# easy_eda_project.net
KiCad netlist of a schematic drawn in EasyEDA Pro
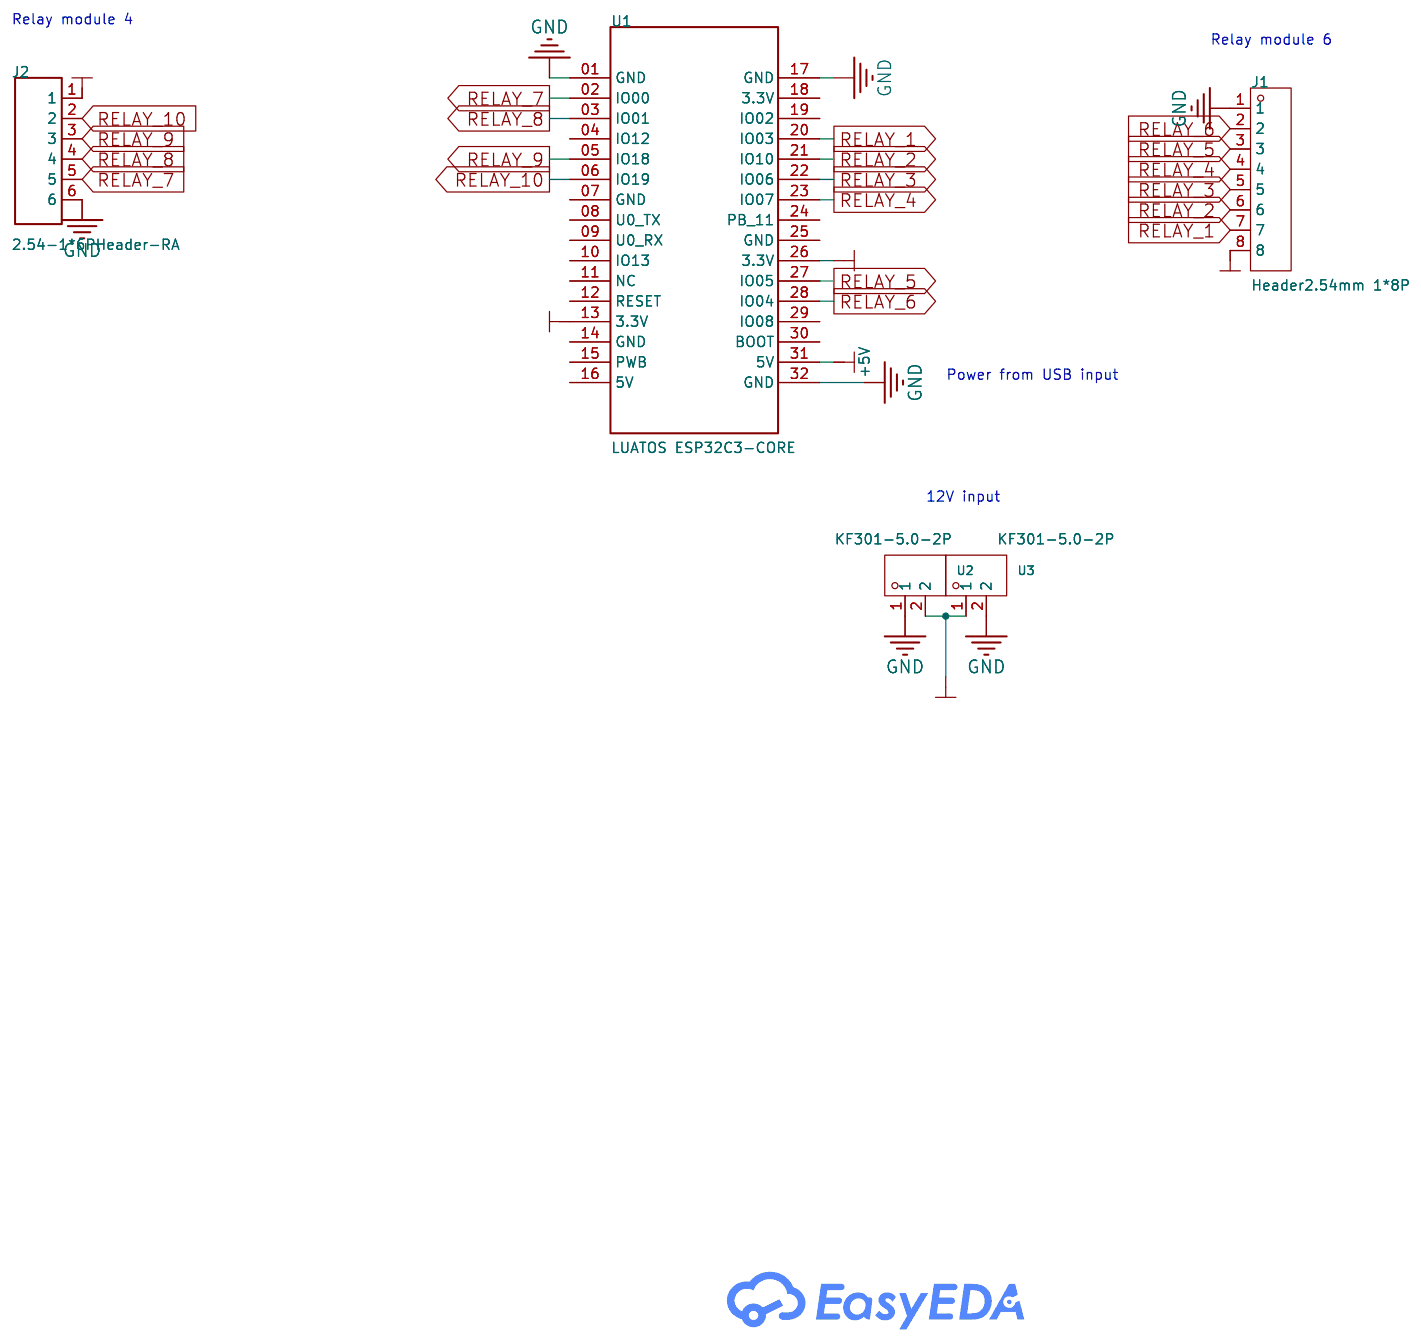
[diagram p0: schematic sheet]

(export (version "E")
  (design (tool "Eeschema 10.0.6"))
  (components
    (comp (ref "J1")
      (value "Header2.54mm 1*8P")
      (fields (field (name "Manufacturer") "ReliaPro"))
      (libsource (lib "easyedapro") (part "Header2.54mm 1*8P"))
    )
    (comp (ref "J2")
      (value "2.54-1*6PHeader-RA")
      (footprint "easyedapro:HDR-TH_6P-P2.54-H-M-W10.0")
      (fields
        (field (name "Manufacturer Part") "2.54-1*6P反弯排针")
        (field (name "Manufacturer") "BOOMELE(博穆精密)")
      )
      (libsource (lib "easyedapro") (part "2.54-1*6PHeader-RA"))
    )
    (comp (ref "U1")
      (value "LUATOS ESP32C3-CORE")
      (fields (field (name "Manufacturer Part") "ESP32C3-CORE") (field (name "Manufacturer") "LuatOS"))
      (libsource (lib "easyedapro") (part "LUATOS ESP32C3-CORE"))
    )
    (comp (ref "U2")
      (value "KF301-5.0-2P")
      (footprint "easyedapro:CONN-TH_P5.00_KF301-5.0-2P")
      (fields (field (name "Manufacturer") "KEFA(科发)"))
      (libsource (lib "easyedapro") (part "KF301-5.0-2P"))
    )
    (comp (ref "U3")
      (value "KF301-5.0-2P")
      (footprint "easyedapro:CONN-TH_P5.00_KF301-5.0-2P")
      (fields (field (name "Manufacturer") "KEFA(科发)"))
      (libsource (lib "easyedapro") (part "KF301-5.0-2P"))
    )
  )
  (nets
    (net (code "1") (name "+5V") (class "Default")
      (node (ref "U1") (pin "31") (pinfunction "5V_31") (pintype "unspecified"))
    )
    (net (code "2") (name "+12V") (class "Default")
      (node (ref "U2") (pin "2") (pinfunction "2_2") (pintype "input"))
      (node (ref "U3") (pin "1") (pinfunction "1_1") (pintype "input"))
    )
    (net (code "3") (name "GND") (class "Default")
      (node (ref "J1") (pin "1") (pinfunction "1_1") (pintype "input"))
      (node (ref "J2") (pin "6") (pinfunction "6_6") (pintype "unspecified"))
      (node (ref "U1") (pin "01") (pinfunction "GND_01") (pintype "unspecified"))
      (node (ref "U1") (pin "17") (pinfunction "GND_17") (pintype "unspecified"))
      (node (ref "U1") (pin "32") (pinfunction "GND_32") (pintype "unspecified"))
      (node (ref "U2") (pin "1") (pinfunction "1_1") (pintype "input"))
      (node (ref "U3") (pin "2") (pinfunction "2_2") (pintype "input"))
    )
    (net (code "4") (name "RELAY_1") (class "Default")
      (node (ref "J1") (pin "7") (pinfunction "7_7") (pintype "input"))
      (node (ref "U1") (pin "20") (pinfunction "IO03_20") (pintype "unspecified"))
    )
    (net (code "5") (name "RELAY_2") (class "Default")
      (node (ref "J1") (pin "6") (pinfunction "6_6") (pintype "input"))
      (node (ref "U1") (pin "21") (pinfunction "IO10_21") (pintype "unspecified"))
    )
    (net (code "6") (name "RELAY_3") (class "Default")
      (node (ref "J1") (pin "5") (pinfunction "5_5") (pintype "input"))
      (node (ref "U1") (pin "22") (pinfunction "IO06_22") (pintype "unspecified"))
    )
    (net (code "7") (name "RELAY_4") (class "Default")
      (node (ref "J1") (pin "4") (pinfunction "4_4") (pintype "input"))
      (node (ref "U1") (pin "23") (pinfunction "IO07_23") (pintype "unspecified"))
    )
    (net (code "8") (name "RELAY_5") (class "Default")
      (node (ref "J1") (pin "3") (pinfunction "3_3") (pintype "input"))
      (node (ref "U1") (pin "27") (pinfunction "IO05_27") (pintype "unspecified"))
    )
    (net (code "9") (name "RELAY_6") (class "Default")
      (node (ref "J1") (pin "2") (pinfunction "2_2") (pintype "input"))
      (node (ref "U1") (pin "28") (pinfunction "IO04_28") (pintype "unspecified"))
    )
    (net (code "10") (name "RELAY_7") (class "Default")
      (node (ref "J2") (pin "5") (pinfunction "5_5") (pintype "unspecified"))
      (node (ref "U1") (pin "02") (pinfunction "IO00_02") (pintype "unspecified"))
    )
    (net (code "11") (name "RELAY_8") (class "Default")
      (node (ref "J2") (pin "4") (pinfunction "4_4") (pintype "unspecified"))
      (node (ref "U1") (pin "03") (pinfunction "IO01_03") (pintype "unspecified"))
    )
    (net (code "12") (name "RELAY_9") (class "Default")
      (node (ref "J2") (pin "3") (pinfunction "3_3") (pintype "unspecified"))
      (node (ref "U1") (pin "05") (pinfunction "IO18_05") (pintype "unspecified"))
    )
    (net (code "13") (name "RELAY_10") (class "Default")
      (node (ref "J2") (pin "2") (pinfunction "2_2") (pintype "unspecified"))
      (node (ref "U1") (pin "06") (pinfunction "IO19_06") (pintype "unspecified"))
    )
    (net (code "14") (name "VCC_3.3") (class "Default")
      (node (ref "J1") (pin "8") (pinfunction "8_8") (pintype "input"))
      (node (ref "J2") (pin "1") (pinfunction "1_1") (pintype "unspecified"))
      (node (ref "U1") (pin "13") (pinfunction "3.3V_13") (pintype "unspecified"))
      (node (ref "U1") (pin "26") (pinfunction "3.3V_26") (pintype "unspecified"))
    )
    (net (code "15") (name "unconnected-(U1-3.3V-Pad18)") (class "Default")
      (node (ref "U1") (pin "18") (pinfunction "3.3V_18") (pintype "unspecified"))
    )
    (net (code "16") (name "unconnected-(U1-5V-Pad16)") (class "Default")
      (node (ref "U1") (pin "16") (pinfunction "5V_16") (pintype "unspecified"))
    )
    (net (code "17") (name "unconnected-(U1-BOOT-Pad30)") (class "Default")
      (node (ref "U1") (pin "30") (pinfunction "BOOT_30") (pintype "unspecified"))
    )
    (net (code "18") (name "unconnected-(U1-GND-Pad07)") (class "Default")
      (node (ref "U1") (pin "07") (pinfunction "GND_07") (pintype "unspecified"))
    )
    (net (code "19") (name "unconnected-(U1-GND-Pad14)") (class "Default")
      (node (ref "U1") (pin "14") (pinfunction "GND_14") (pintype "unspecified"))
    )
    (net (code "20") (name "unconnected-(U1-GND-Pad25)") (class "Default")
      (node (ref "U1") (pin "25") (pinfunction "GND_25") (pintype "unspecified"))
    )
    (net (code "21") (name "unconnected-(U1-IO02-Pad19)") (class "Default")
      (node (ref "U1") (pin "19") (pinfunction "IO02_19") (pintype "unspecified"))
    )
    (net (code "22") (name "unconnected-(U1-IO08-Pad29)") (class "Default")
      (node (ref "U1") (pin "29") (pinfunction "IO08_29") (pintype "unspecified"))
    )
    (net (code "23") (name "unconnected-(U1-IO12-Pad04)") (class "Default")
      (node (ref "U1") (pin "04") (pinfunction "IO12_04") (pintype "unspecified"))
    )
    (net (code "24") (name "unconnected-(U1-IO13-Pad10)") (class "Default")
      (node (ref "U1") (pin "10") (pinfunction "IO13_10") (pintype "unspecified"))
    )
    (net (code "25") (name "unconnected-(U1-NC-Pad11)") (class "Default")
      (node (ref "U1") (pin "11") (pinfunction "NC_11") (pintype "unspecified"))
    )
    (net (code "26") (name "unconnected-(U1-PB_11-Pad24)") (class "Default")
      (node (ref "U1") (pin "24") (pinfunction "PB_11_24") (pintype "unspecified"))
    )
    (net (code "27") (name "unconnected-(U1-PWB-Pad15)") (class "Default")
      (node (ref "U1") (pin "15") (pinfunction "PWB_15") (pintype "unspecified"))
    )
    (net (code "28") (name "unconnected-(U1-RESET-Pad12)") (class "Default")
      (node (ref "U1") (pin "12") (pinfunction "RESET_12") (pintype "unspecified"))
    )
    (net (code "29") (name "unconnected-(U1-U0_RX-Pad09)") (class "Default")
      (node (ref "U1") (pin "09") (pinfunction "U0_RX_09") (pintype "unspecified"))
    )
    (net (code "30") (name "unconnected-(U1-U0_TX-Pad08)") (class "Default")
      (node (ref "U1") (pin "08") (pinfunction "U0_TX_08") (pintype "unspecified"))
    )
  )
)
